# detection_input.net
KiCad netlist of a schematic drawn in EAGLE
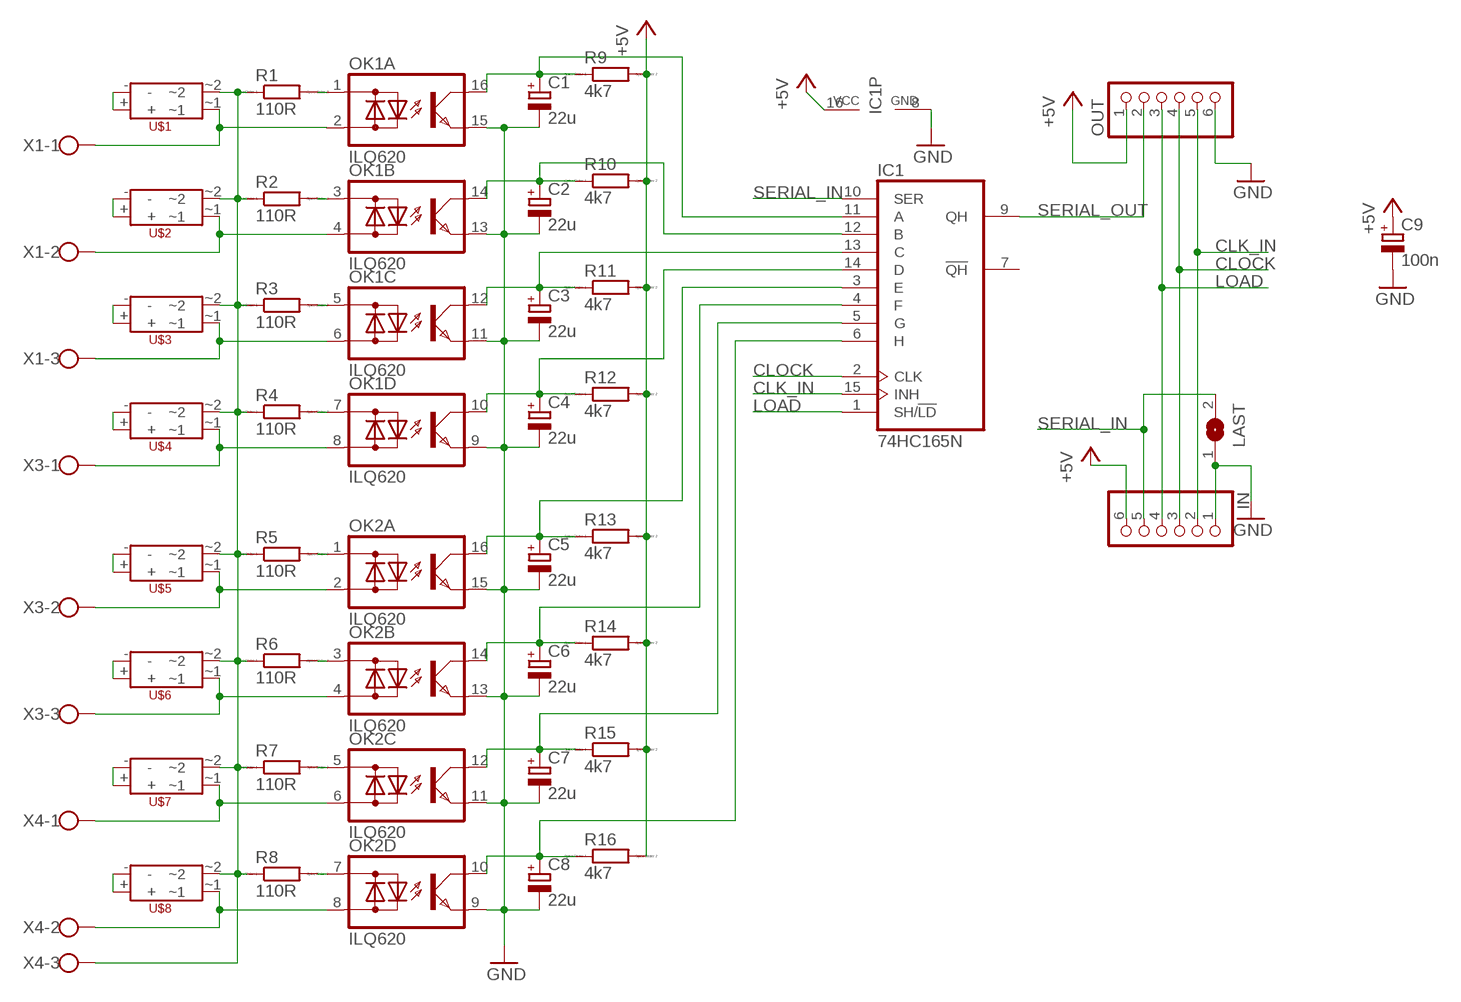
[diagram p0: schematic, sheet 1]

(export (version "E")
  (design (tool "Eeschema 10.0.6"))
  (components
    (comp (ref "C1")
      (value "22u")
      (footprint "eagle-import:E2-4")
      (libsource (lib "eagle-import") (part "CPOL-EUE2-4"))
    )
    (comp (ref "C2")
      (value "22u")
      (footprint "eagle-import:E2-4")
      (libsource (lib "eagle-import") (part "CPOL-EUE2-4"))
    )
    (comp (ref "C3")
      (value "22u")
      (footprint "eagle-import:E2-4")
      (libsource (lib "eagle-import") (part "CPOL-EUE2-4"))
    )
    (comp (ref "C4")
      (value "22u")
      (footprint "eagle-import:E2-4")
      (libsource (lib "eagle-import") (part "CPOL-EUE2-4"))
    )
    (comp (ref "C5")
      (value "22u")
      (footprint "eagle-import:E2-4")
      (libsource (lib "eagle-import") (part "CPOL-EUE2-4"))
    )
    (comp (ref "C6")
      (value "22u")
      (footprint "eagle-import:E2-4")
      (libsource (lib "eagle-import") (part "CPOL-EUE2-4"))
    )
    (comp (ref "C7")
      (value "22u")
      (footprint "eagle-import:E2-4")
      (libsource (lib "eagle-import") (part "CPOL-EUE2-4"))
    )
    (comp (ref "C8")
      (value "22u")
      (footprint "eagle-import:E2-4")
      (libsource (lib "eagle-import") (part "CPOL-EUE2-4"))
    )
    (comp (ref "C9")
      (value "100n")
      (footprint "eagle-import:A_3216-18W")
      (libsource (lib "eagle-import") (part "CPOL-EUA/3216-18W"))
    )
    (comp (ref "IC1")
      (value "74HC165N")
      (footprint "eagle-import:DIL16")
      (libsource (lib "eagle-import") (part "74165NHC"))
    )
    (comp (ref "IN")
      (value "PINHD-1X6")
      (footprint "eagle-import:1X06")
      (libsource (lib "eagle-import") (part "PINHD-1X6"))
    )
    (comp (ref "LAST")
      (value "SJ")
      (footprint "eagle-import:SJ")
      (libsource (lib "eagle-import") (part "SJ"))
    )
    (comp (ref "OK1")
      (value "ILQ620")
      (footprint "eagle-import:DIL16")
      (fields (field (name "MF") "VISHAY/TELEFUNKEN"))
      (libsource (lib "eagle-import") (part "ILQ620"))
    )
    (comp (ref "OK2")
      (value "ILQ620")
      (footprint "eagle-import:DIL16")
      (fields (field (name "MF") "VISHAY/TELEFUNKEN"))
      (libsource (lib "eagle-import") (part "ILQ620"))
    )
    (comp (ref "OUT")
      (value "PINHD-1X6")
      (footprint "eagle-import:1X06")
      (libsource (lib "eagle-import") (part "PINHD-1X6"))
    )
    (comp (ref "R1")
      (value "110R")
      (footprint "eagle-import:0204_7")
      (libsource (lib "eagle-import") (part "R0204/7"))
    )
    (comp (ref "R2")
      (value "110R")
      (footprint "eagle-import:0204_7")
      (libsource (lib "eagle-import") (part "R0204/7"))
    )
    (comp (ref "R3")
      (value "110R")
      (footprint "eagle-import:0204_7")
      (libsource (lib "eagle-import") (part "R0204/7"))
    )
    (comp (ref "R4")
      (value "110R")
      (footprint "eagle-import:0204_7")
      (libsource (lib "eagle-import") (part "R0204/7"))
    )
    (comp (ref "R5")
      (value "110R")
      (footprint "eagle-import:0204_7")
      (libsource (lib "eagle-import") (part "R0204/7"))
    )
    (comp (ref "R6")
      (value "110R")
      (footprint "eagle-import:0204_7")
      (libsource (lib "eagle-import") (part "R0204/7"))
    )
    (comp (ref "R7")
      (value "110R")
      (footprint "eagle-import:0204_7")
      (libsource (lib "eagle-import") (part "R0204/7"))
    )
    (comp (ref "R8")
      (value "110R")
      (footprint "eagle-import:0204_7")
      (libsource (lib "eagle-import") (part "R0204/7"))
    )
    (comp (ref "R9")
      (value "4k7")
      (footprint "eagle-import:0204_7")
      (libsource (lib "eagle-import") (part "R0204/7"))
    )
    (comp (ref "R10")
      (value "4k7")
      (footprint "eagle-import:0204_7")
      (libsource (lib "eagle-import") (part "R0204/7"))
    )
    (comp (ref "R11")
      (value "4k7")
      (footprint "eagle-import:0204_7")
      (libsource (lib "eagle-import") (part "R0204/7"))
    )
    (comp (ref "R12")
      (value "4k7")
      (footprint "eagle-import:0204_7")
      (libsource (lib "eagle-import") (part "R0204/7"))
    )
    (comp (ref "R13")
      (value "4k7")
      (footprint "eagle-import:0204_7")
      (libsource (lib "eagle-import") (part "R0204/7"))
    )
    (comp (ref "R14")
      (value "4k7")
      (footprint "eagle-import:0204_7")
      (libsource (lib "eagle-import") (part "R0204/7"))
    )
    (comp (ref "R15")
      (value "4k7")
      (footprint "eagle-import:0204_7")
      (libsource (lib "eagle-import") (part "R0204/7"))
    )
    (comp (ref "R16")
      (value "4k7")
      (footprint "eagle-import:0204_7")
      (libsource (lib "eagle-import") (part "R0204/7"))
    )
    (comp (ref "U$1")
      (value "2W10")
      (footprint "eagle-import:2W10")
      (libsource (lib "eagle-import") (part "2W10"))
    )
    (comp (ref "U$2")
      (value "2W10")
      (footprint "eagle-import:2W10")
      (libsource (lib "eagle-import") (part "2W10"))
    )
    (comp (ref "U$3")
      (value "2W10")
      (footprint "eagle-import:2W10")
      (libsource (lib "eagle-import") (part "2W10"))
    )
    (comp (ref "U$4")
      (value "2W10")
      (footprint "eagle-import:2W10")
      (libsource (lib "eagle-import") (part "2W10"))
    )
    (comp (ref "U$5")
      (value "2W10")
      (footprint "eagle-import:2W10")
      (libsource (lib "eagle-import") (part "2W10"))
    )
    (comp (ref "U$6")
      (value "2W10")
      (footprint "eagle-import:2W10")
      (libsource (lib "eagle-import") (part "2W10"))
    )
    (comp (ref "U$7")
      (value "2W10")
      (footprint "eagle-import:2W10")
      (libsource (lib "eagle-import") (part "2W10"))
    )
    (comp (ref "U$8")
      (value "2W10")
      (footprint "eagle-import:2W10")
      (libsource (lib "eagle-import") (part "2W10"))
    )
    (comp (ref "X1")
      (value "W237-103")
      (footprint "eagle-import:W237-103")
      (fields (field (name "MPN") "237-103"))
      (libsource (lib "eagle-import") (part "W237-103"))
    )
    (comp (ref "X3")
      (value "W237-103")
      (footprint "eagle-import:W237-103")
      (fields (field (name "MPN") "237-103"))
      (libsource (lib "eagle-import") (part "W237-103"))
    )
    (comp (ref "X4")
      (value "W237-103")
      (footprint "eagle-import:W237-103")
      (fields (field (name "MPN") "237-103"))
      (libsource (lib "eagle-import") (part "W237-103"))
    )
  )
  (nets
    (net (code "1") (name "+5V") (class "Default")
      (node (ref "C9") (pin "+") (pinfunction "+_+") (pintype "passive"))
      (node (ref "IC1") (pin "16") (pinfunction "VCC_16") (pintype "power_in"))
      (node (ref "IN") (pin "6") (pinfunction "6_6") (pintype "passive"))
      (node (ref "OUT") (pin "1") (pinfunction "1_1") (pintype "passive"))
      (node (ref "R10") (pin "2") (pinfunction "2_2") (pintype "passive"))
      (node (ref "R11") (pin "2") (pinfunction "2_2") (pintype "passive"))
      (node (ref "R12") (pin "2") (pinfunction "2_2") (pintype "passive"))
      (node (ref "R13") (pin "2") (pinfunction "2_2") (pintype "passive"))
      (node (ref "R14") (pin "2") (pinfunction "2_2") (pintype "passive"))
      (node (ref "R15") (pin "2") (pinfunction "2_2") (pintype "passive"))
      (node (ref "R16") (pin "2") (pinfunction "2_2") (pintype "passive"))
      (node (ref "R9") (pin "2") (pinfunction "2_2") (pintype "passive"))
    )
    (net (code "2") (name "/CLK_IN") (class "Default")
      (node (ref "IC1") (pin "15") (pinfunction "INH_15") (pintype "input"))
      (node (ref "IN") (pin "2") (pinfunction "2_2") (pintype "passive"))
      (node (ref "OUT") (pin "5") (pinfunction "5_5") (pintype "passive"))
    )
    (net (code "3") (name "/CLOCK") (class "Default")
      (node (ref "IC1") (pin "2") (pinfunction "CLK_2") (pintype "input"))
      (node (ref "IN") (pin "3") (pinfunction "3_3") (pintype "passive"))
      (node (ref "OUT") (pin "4") (pinfunction "4_4") (pintype "passive"))
    )
    (net (code "4") (name "/LOAD") (class "Default")
      (node (ref "IC1") (pin "1") (pinfunction "SH/~{LD}_1") (pintype "input"))
      (node (ref "IN") (pin "4") (pinfunction "4_4") (pintype "passive"))
      (node (ref "OUT") (pin "3") (pinfunction "3_3") (pintype "passive"))
    )
    (net (code "5") (name "/SERIAL_IN") (class "Default")
      (node (ref "IC1") (pin "10") (pinfunction "SER_10") (pintype "input"))
      (node (ref "IN") (pin "5") (pinfunction "5_5") (pintype "passive"))
      (node (ref "LAST") (pin "2") (pinfunction "2_2") (pintype "passive"))
    )
    (net (code "6") (name "/SERIAL_OUT") (class "Default")
      (node (ref "IC1") (pin "9") (pinfunction "QH_9") (pintype "output"))
      (node (ref "OUT") (pin "2") (pinfunction "2_2") (pintype "passive"))
    )
    (net (code "7") (name "GND") (class "Default")
      (node (ref "C1") (pin "-") (pinfunction "-_-") (pintype "passive"))
      (node (ref "C2") (pin "-") (pinfunction "-_-") (pintype "passive"))
      (node (ref "C3") (pin "-") (pinfunction "-_-") (pintype "passive"))
      (node (ref "C4") (pin "-") (pinfunction "-_-") (pintype "passive"))
      (node (ref "C5") (pin "-") (pinfunction "-_-") (pintype "passive"))
      (node (ref "C6") (pin "-") (pinfunction "-_-") (pintype "passive"))
      (node (ref "C7") (pin "-") (pinfunction "-_-") (pintype "passive"))
      (node (ref "C8") (pin "-") (pinfunction "-_-") (pintype "passive"))
      (node (ref "C9") (pin "-") (pinfunction "-_-") (pintype "passive"))
      (node (ref "IC1") (pin "8") (pinfunction "GND_8") (pintype "power_in"))
      (node (ref "IN") (pin "1") (pinfunction "1_1") (pintype "passive"))
      (node (ref "LAST") (pin "1") (pinfunction "1_1") (pintype "passive"))
      (node (ref "OK1") (pin "11") (pinfunction "E_11") (pintype "passive"))
      (node (ref "OK1") (pin "13") (pinfunction "E_13") (pintype "passive"))
      (node (ref "OK1") (pin "15") (pinfunction "E_15") (pintype "passive"))
      (node (ref "OK1") (pin "9") (pinfunction "E_9") (pintype "passive"))
      (node (ref "OK2") (pin "11") (pinfunction "E_11") (pintype "passive"))
      (node (ref "OK2") (pin "13") (pinfunction "E_13") (pintype "passive"))
      (node (ref "OK2") (pin "15") (pinfunction "E_15") (pintype "passive"))
      (node (ref "OK2") (pin "9") (pinfunction "E_9") (pintype "passive"))
      (node (ref "OUT") (pin "6") (pinfunction "6_6") (pintype "passive"))
    )
    (net (code "8") (name "Net-(IC1A-A)") (class "Default")
      (node (ref "C1") (pin "+") (pinfunction "+_+") (pintype "passive"))
      (node (ref "IC1") (pin "11") (pinfunction "A_11") (pintype "input"))
      (node (ref "OK1") (pin "16") (pinfunction "C_16") (pintype "passive"))
      (node (ref "R9") (pin "1") (pinfunction "1_1") (pintype "passive"))
    )
    (net (code "9") (name "Net-(IC1A-B)") (class "Default")
      (node (ref "C2") (pin "+") (pinfunction "+_+") (pintype "passive"))
      (node (ref "IC1") (pin "12") (pinfunction "B_12") (pintype "input"))
      (node (ref "OK1") (pin "14") (pinfunction "C_14") (pintype "passive"))
      (node (ref "R10") (pin "1") (pinfunction "1_1") (pintype "passive"))
    )
    (net (code "10") (name "Net-(IC1A-C)") (class "Default")
      (node (ref "C3") (pin "+") (pinfunction "+_+") (pintype "passive"))
      (node (ref "IC1") (pin "13") (pinfunction "C_13") (pintype "input"))
      (node (ref "OK1") (pin "12") (pinfunction "C_12") (pintype "passive"))
      (node (ref "R11") (pin "1") (pinfunction "1_1") (pintype "passive"))
    )
    (net (code "11") (name "Net-(IC1A-D)") (class "Default")
      (node (ref "C4") (pin "+") (pinfunction "+_+") (pintype "passive"))
      (node (ref "IC1") (pin "14") (pinfunction "D_14") (pintype "input"))
      (node (ref "OK1") (pin "10") (pinfunction "C_10") (pintype "passive"))
      (node (ref "R12") (pin "1") (pinfunction "1_1") (pintype "passive"))
    )
    (net (code "12") (name "Net-(IC1A-E)") (class "Default")
      (node (ref "C5") (pin "+") (pinfunction "+_+") (pintype "passive"))
      (node (ref "IC1") (pin "3") (pinfunction "E_3") (pintype "input"))
      (node (ref "OK2") (pin "16") (pinfunction "C_16") (pintype "passive"))
      (node (ref "R13") (pin "1") (pinfunction "1_1") (pintype "passive"))
    )
    (net (code "13") (name "Net-(IC1A-F)") (class "Default")
      (node (ref "C6") (pin "+") (pinfunction "+_+") (pintype "passive"))
      (node (ref "IC1") (pin "4") (pinfunction "F_4") (pintype "input"))
      (node (ref "OK2") (pin "14") (pinfunction "C_14") (pintype "passive"))
      (node (ref "R14") (pin "1") (pinfunction "1_1") (pintype "passive"))
    )
    (net (code "14") (name "Net-(IC1A-G)") (class "Default")
      (node (ref "C7") (pin "+") (pinfunction "+_+") (pintype "passive"))
      (node (ref "IC1") (pin "5") (pinfunction "G_5") (pintype "input"))
      (node (ref "OK2") (pin "12") (pinfunction "C_12") (pintype "passive"))
      (node (ref "R15") (pin "1") (pinfunction "1_1") (pintype "passive"))
    )
    (net (code "15") (name "Net-(IC1A-H)") (class "Default")
      (node (ref "C8") (pin "+") (pinfunction "+_+") (pintype "passive"))
      (node (ref "IC1") (pin "6") (pinfunction "H_6") (pintype "input"))
      (node (ref "OK2") (pin "10") (pinfunction "C_10") (pintype "passive"))
      (node (ref "R16") (pin "1") (pinfunction "1_1") (pintype "passive"))
    )
    (net (code "16") (name "Net-(OK1A-AC1)") (class "Default")
      (node (ref "OK1") (pin "1") (pinfunction "AC1_1") (pintype "passive"))
      (node (ref "R1") (pin "2") (pinfunction "2_2") (pintype "passive"))
    )
    (net (code "17") (name "Net-(OK1A-AC2)") (class "Default")
      (node (ref "OK1") (pin "2") (pinfunction "AC2_2") (pintype "passive"))
      (node (ref "U$1") (pin "~1") (pinfunction "~{1}_~1") (pintype "bidirectional"))
      (node (ref "X1") (pin "1") (pinfunction "KL_1") (pintype "passive"))
    )
    (net (code "18") (name "Net-(OK1B-AC1)") (class "Default")
      (node (ref "OK1") (pin "3") (pinfunction "AC1_3") (pintype "passive"))
      (node (ref "R2") (pin "2") (pinfunction "2_2") (pintype "passive"))
    )
    (net (code "19") (name "Net-(OK1B-AC2)") (class "Default")
      (node (ref "OK1") (pin "4") (pinfunction "AC2_4") (pintype "passive"))
      (node (ref "U$2") (pin "~1") (pinfunction "~{1}_~1") (pintype "bidirectional"))
      (node (ref "X1") (pin "2") (pinfunction "KL_2") (pintype "passive"))
    )
    (net (code "20") (name "Net-(OK1C-AC1)") (class "Default")
      (node (ref "OK1") (pin "5") (pinfunction "AC1_5") (pintype "passive"))
      (node (ref "R3") (pin "2") (pinfunction "2_2") (pintype "passive"))
    )
    (net (code "21") (name "Net-(OK1C-AC2)") (class "Default")
      (node (ref "OK1") (pin "6") (pinfunction "AC2_6") (pintype "passive"))
      (node (ref "U$3") (pin "~1") (pinfunction "~{1}_~1") (pintype "bidirectional"))
      (node (ref "X1") (pin "3") (pinfunction "KL_3") (pintype "passive"))
    )
    (net (code "22") (name "Net-(OK1D-AC1)") (class "Default")
      (node (ref "OK1") (pin "7") (pinfunction "AC1_7") (pintype "passive"))
      (node (ref "R4") (pin "2") (pinfunction "2_2") (pintype "passive"))
    )
    (net (code "23") (name "Net-(OK1D-AC2)") (class "Default")
      (node (ref "OK1") (pin "8") (pinfunction "AC2_8") (pintype "passive"))
      (node (ref "U$4") (pin "~1") (pinfunction "~{1}_~1") (pintype "bidirectional"))
      (node (ref "X3") (pin "1") (pinfunction "KL_1") (pintype "passive"))
    )
    (net (code "24") (name "Net-(OK2A-AC1)") (class "Default")
      (node (ref "OK2") (pin "1") (pinfunction "AC1_1") (pintype "passive"))
      (node (ref "R5") (pin "2") (pinfunction "2_2") (pintype "passive"))
    )
    (net (code "25") (name "Net-(OK2A-AC2)") (class "Default")
      (node (ref "OK2") (pin "2") (pinfunction "AC2_2") (pintype "passive"))
      (node (ref "U$5") (pin "~1") (pinfunction "~{1}_~1") (pintype "bidirectional"))
      (node (ref "X3") (pin "2") (pinfunction "KL_2") (pintype "passive"))
    )
    (net (code "26") (name "Net-(OK2B-AC1)") (class "Default")
      (node (ref "OK2") (pin "3") (pinfunction "AC1_3") (pintype "passive"))
      (node (ref "R6") (pin "2") (pinfunction "2_2") (pintype "passive"))
    )
    (net (code "27") (name "Net-(OK2B-AC2)") (class "Default")
      (node (ref "OK2") (pin "4") (pinfunction "AC2_4") (pintype "passive"))
      (node (ref "U$6") (pin "~1") (pinfunction "~{1}_~1") (pintype "bidirectional"))
      (node (ref "X3") (pin "3") (pinfunction "KL_3") (pintype "passive"))
    )
    (net (code "28") (name "Net-(OK2C-AC1)") (class "Default")
      (node (ref "OK2") (pin "5") (pinfunction "AC1_5") (pintype "passive"))
      (node (ref "R7") (pin "2") (pinfunction "2_2") (pintype "passive"))
    )
    (net (code "29") (name "Net-(OK2C-AC2)") (class "Default")
      (node (ref "OK2") (pin "6") (pinfunction "AC2_6") (pintype "passive"))
      (node (ref "U$7") (pin "~1") (pinfunction "~{1}_~1") (pintype "bidirectional"))
      (node (ref "X4") (pin "1") (pinfunction "KL_1") (pintype "passive"))
    )
    (net (code "30") (name "Net-(OK2D-AC1)") (class "Default")
      (node (ref "OK2") (pin "7") (pinfunction "AC1_7") (pintype "passive"))
      (node (ref "R8") (pin "2") (pinfunction "2_2") (pintype "passive"))
    )
    (net (code "31") (name "Net-(OK2D-AC2)") (class "Default")
      (node (ref "OK2") (pin "8") (pinfunction "AC2_8") (pintype "passive"))
      (node (ref "U$8") (pin "~1") (pinfunction "~{1}_~1") (pintype "bidirectional"))
      (node (ref "X4") (pin "2") (pinfunction "KL_2") (pintype "passive"))
    )
    (net (code "32") (name "Net-(U$1-Pad+)") (class "Default")
      (node (ref "U$1") (pin "+") (pinfunction "+_+") (pintype "bidirectional"))
      (node (ref "U$1") (pin "-") (pinfunction "-_-") (pintype "bidirectional"))
    )
    (net (code "33") (name "Net-(U$1-~{2})") (class "Default")
      (node (ref "R1") (pin "1") (pinfunction "1_1") (pintype "passive"))
      (node (ref "R2") (pin "1") (pinfunction "1_1") (pintype "passive"))
      (node (ref "R3") (pin "1") (pinfunction "1_1") (pintype "passive"))
      (node (ref "R4") (pin "1") (pinfunction "1_1") (pintype "passive"))
      (node (ref "R5") (pin "1") (pinfunction "1_1") (pintype "passive"))
      (node (ref "R6") (pin "1") (pinfunction "1_1") (pintype "passive"))
      (node (ref "R7") (pin "1") (pinfunction "1_1") (pintype "passive"))
      (node (ref "R8") (pin "1") (pinfunction "1_1") (pintype "passive"))
      (node (ref "U$1") (pin "~2") (pinfunction "~{2}_~2") (pintype "bidirectional"))
      (node (ref "U$2") (pin "~2") (pinfunction "~{2}_~2") (pintype "bidirectional"))
      (node (ref "U$3") (pin "~2") (pinfunction "~{2}_~2") (pintype "bidirectional"))
      (node (ref "U$4") (pin "~2") (pinfunction "~{2}_~2") (pintype "bidirectional"))
      (node (ref "U$5") (pin "~2") (pinfunction "~{2}_~2") (pintype "bidirectional"))
      (node (ref "U$6") (pin "~2") (pinfunction "~{2}_~2") (pintype "bidirectional"))
      (node (ref "U$7") (pin "~2") (pinfunction "~{2}_~2") (pintype "bidirectional"))
      (node (ref "U$8") (pin "~2") (pinfunction "~{2}_~2") (pintype "bidirectional"))
      (node (ref "X4") (pin "3") (pinfunction "KL_3") (pintype "passive"))
    )
    (net (code "34") (name "Net-(U$2-Pad+)") (class "Default")
      (node (ref "U$2") (pin "+") (pinfunction "+_+") (pintype "bidirectional"))
      (node (ref "U$2") (pin "-") (pinfunction "-_-") (pintype "bidirectional"))
    )
    (net (code "35") (name "Net-(U$3-Pad+)") (class "Default")
      (node (ref "U$3") (pin "+") (pinfunction "+_+") (pintype "bidirectional"))
      (node (ref "U$3") (pin "-") (pinfunction "-_-") (pintype "bidirectional"))
    )
    (net (code "36") (name "Net-(U$4-Pad+)") (class "Default")
      (node (ref "U$4") (pin "+") (pinfunction "+_+") (pintype "bidirectional"))
      (node (ref "U$4") (pin "-") (pinfunction "-_-") (pintype "bidirectional"))
    )
    (net (code "37") (name "Net-(U$5-Pad+)") (class "Default")
      (node (ref "U$5") (pin "+") (pinfunction "+_+") (pintype "bidirectional"))
      (node (ref "U$5") (pin "-") (pinfunction "-_-") (pintype "bidirectional"))
    )
    (net (code "38") (name "Net-(U$6-Pad+)") (class "Default")
      (node (ref "U$6") (pin "+") (pinfunction "+_+") (pintype "bidirectional"))
      (node (ref "U$6") (pin "-") (pinfunction "-_-") (pintype "bidirectional"))
    )
    (net (code "39") (name "Net-(U$7-Pad+)") (class "Default")
      (node (ref "U$7") (pin "+") (pinfunction "+_+") (pintype "bidirectional"))
      (node (ref "U$7") (pin "-") (pinfunction "-_-") (pintype "bidirectional"))
    )
    (net (code "40") (name "Net-(U$8-Pad+)") (class "Default")
      (node (ref "U$8") (pin "+") (pinfunction "+_+") (pintype "bidirectional"))
      (node (ref "U$8") (pin "-") (pinfunction "-_-") (pintype "bidirectional"))
    )
    (net (code "41") (name "unconnected-(IC1A-~{QH}-Pad7)") (class "Default")
      (node (ref "IC1") (pin "7") (pinfunction "~{QH}_7") (pintype "output"))
    )
  )
)
